# PCB.net
KiCad netlist of a schematic drawn in EasyEDA Pro
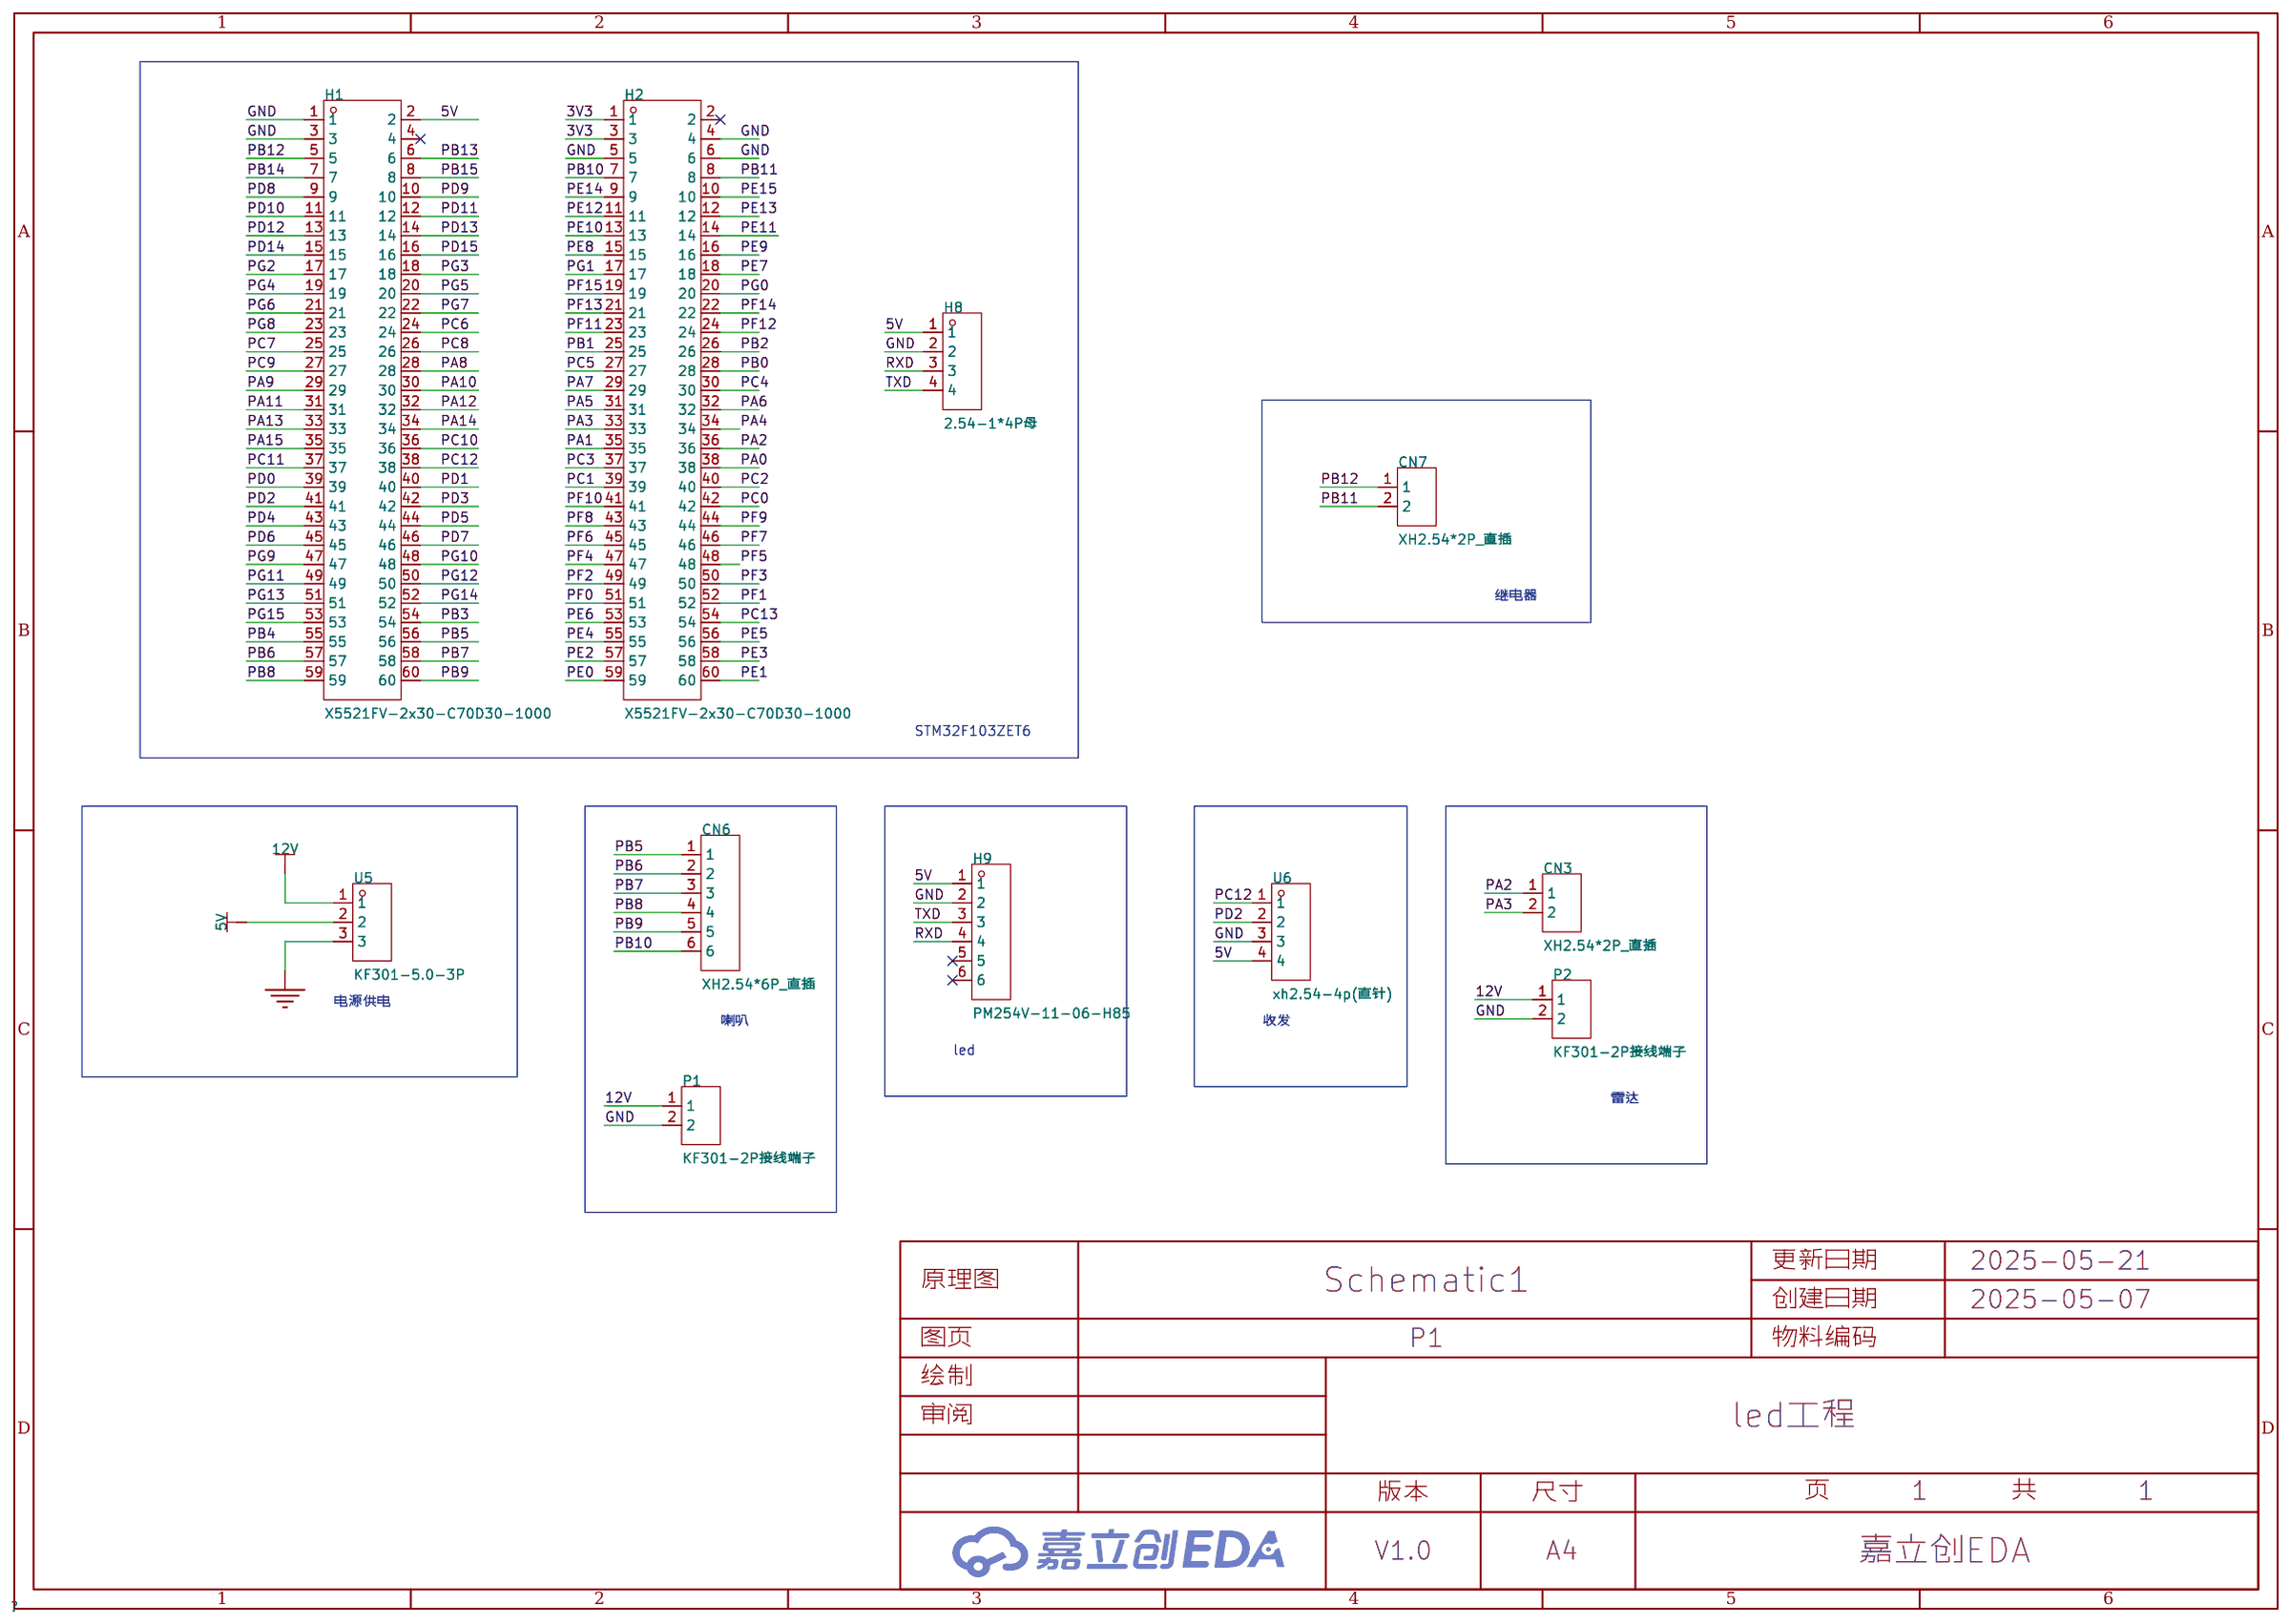
[diagram p0: schematic sheet]

(export (version "E")
  (design (tool "Eeschema 10.0.6"))
  (components
    (comp (ref "CN3")
      (value "XH2.54*2P_直插")
      (footprint "easyedapro:CONN-TH_2P-P2.50-XH2.54-2P")
      (libsource (lib "easyedapro") (part "XH2.54*2P_直插"))
    )
    (comp (ref "CN6")
      (value "XH2.54*6P_直插")
      (footprint "easyedapro:CONN-TH_XH2.54-6P")
      (libsource (lib "easyedapro") (part "XH2.54*6P_直插"))
    )
    (comp (ref "CN7")
      (value "XH2.54*2P_直插")
      (footprint "easyedapro:CONN-TH_2P-P2.50-XH2.54-2P")
      (libsource (lib "easyedapro") (part "XH2.54*2P_直插"))
    )
    (comp (ref "H1")
      (value "X5521FV-2x30-C70D30-1000")
      (footprint "easyedapro:HDR-TH_60P-P2.54-V-F-R2-C30-S2.54-3")
      (fields (field (name "Manufacturer") "XKB Connectivity(中国星坤)"))
      (libsource (lib "easyedapro") (part "X5521FV-2X30-C70D30-1000"))
    )
    (comp (ref "H2")
      (value "X5521FV-2x30-C70D30-1000")
      (footprint "easyedapro:HDR-TH_60P-P2.54-V-F-R2-C30-S2.54-3")
      (fields (field (name "Manufacturer") "XKB Connectivity(中国星坤)"))
      (libsource (lib "easyedapro") (part "X5521FV-2X30-C70D30-1000"))
    )
    (comp (ref "H8")
      (value "2.54-1*4P母")
      (footprint "easyedapro:HDR-TH_4P-P2.54-V-F")
      (fields (field (name "Manufacturer") "BOOMELE(博穆精密)"))
      (libsource (lib "easyedapro") (part "2.54-1*4P母"))
    )
    (comp (ref "H9")
      (value "PM254V-11-06-H85")
      (footprint "easyedapro:HDR-TH_6P-P2.54-V-F")
      (fields (field (name "Manufacturer") "XFCN(兴飞)"))
      (libsource (lib "easyedapro") (part "PM254V-11-06-H85"))
    )
    (comp (ref "P1")
      (value "KF301-2P接线端子")
      (footprint "easyedapro:CONN-TH_XY301V-A-5.0-2P")
      (libsource (lib "easyedapro") (part "KF301-2P接线端子"))
    )
    (comp (ref "P2")
      (value "KF301-2P接线端子")
      (footprint "easyedapro:CONN-TH_XY301V-A-5.0-2P")
      (libsource (lib "easyedapro") (part "KF301-2P接线端子"))
    )
    (comp (ref "U5")
      (value "KF301-5.0-3P")
      (footprint "easyedapro:CONN-TH_3P-P5.00_KF301-5.0-3P")
      (fields (field (name "Manufacturer") "KEFA(科发)"))
      (libsource (lib "easyedapro") (part "KF301-5.0-3P"))
    )
    (comp (ref "U6")
      (value "xh2.54-4p(直针)")
      (footprint "easyedapro:CONN-TH_4P-P2.50-XH2.54-4P")
      (libsource (lib "easyedapro") (part "XH2.54-4P(直针)"))
    )
  )
  (nets
    (net (code "1") (name "/3V3") (class "Default")
      (node (ref "H2") (pin "1") (pinfunction "1_1") (pintype "unspecified"))
      (node (ref "H2") (pin "3") (pinfunction "3_3") (pintype "unspecified"))
    )
    (net (code "2") (name "/PA0") (class "Default")
      (node (ref "H2") (pin "38") (pinfunction "38_38") (pintype "unspecified"))
    )
    (net (code "3") (name "/PA1") (class "Default")
      (node (ref "H2") (pin "35") (pinfunction "35_35") (pintype "unspecified"))
    )
    (net (code "4") (name "/PA2") (class "Default")
      (node (ref "CN3") (pin "1") (pinfunction "1_1") (pintype "unspecified"))
      (node (ref "H2") (pin "36") (pinfunction "36_36") (pintype "unspecified"))
    )
    (net (code "5") (name "/PA3") (class "Default")
      (node (ref "CN3") (pin "2") (pinfunction "2_2") (pintype "unspecified"))
      (node (ref "H2") (pin "33") (pinfunction "33_33") (pintype "unspecified"))
    )
    (net (code "6") (name "/PA4") (class "Default")
      (node (ref "H2") (pin "34") (pinfunction "34_34") (pintype "unspecified"))
    )
    (net (code "7") (name "/PA5") (class "Default")
      (node (ref "H2") (pin "31") (pinfunction "31_31") (pintype "unspecified"))
    )
    (net (code "8") (name "/PA6") (class "Default")
      (node (ref "H2") (pin "32") (pinfunction "32_32") (pintype "unspecified"))
    )
    (net (code "9") (name "/PA7") (class "Default")
      (node (ref "H2") (pin "29") (pinfunction "29_29") (pintype "unspecified"))
    )
    (net (code "10") (name "/PA8") (class "Default")
      (node (ref "H1") (pin "28") (pinfunction "28_28") (pintype "unspecified"))
    )
    (net (code "11") (name "/PA9") (class "Default")
      (node (ref "H1") (pin "29") (pinfunction "29_29") (pintype "unspecified"))
    )
    (net (code "12") (name "/PA10") (class "Default")
      (node (ref "H1") (pin "30") (pinfunction "30_30") (pintype "unspecified"))
    )
    (net (code "13") (name "/PA11") (class "Default")
      (node (ref "H1") (pin "31") (pinfunction "31_31") (pintype "unspecified"))
    )
    (net (code "14") (name "/PA12") (class "Default")
      (node (ref "H1") (pin "32") (pinfunction "32_32") (pintype "unspecified"))
    )
    (net (code "15") (name "/PA13") (class "Default")
      (node (ref "H1") (pin "33") (pinfunction "33_33") (pintype "unspecified"))
    )
    (net (code "16") (name "/PA14") (class "Default")
      (node (ref "H1") (pin "34") (pinfunction "34_34") (pintype "unspecified"))
    )
    (net (code "17") (name "/PA15") (class "Default")
      (node (ref "H1") (pin "35") (pinfunction "35_35") (pintype "unspecified"))
    )
    (net (code "18") (name "/PB0") (class "Default")
      (node (ref "H2") (pin "28") (pinfunction "28_28") (pintype "unspecified"))
    )
    (net (code "19") (name "/PB1") (class "Default")
      (node (ref "H2") (pin "25") (pinfunction "25_25") (pintype "unspecified"))
    )
    (net (code "20") (name "/PB2") (class "Default")
      (node (ref "H2") (pin "26") (pinfunction "26_26") (pintype "unspecified"))
    )
    (net (code "21") (name "/PB3") (class "Default")
      (node (ref "H1") (pin "54") (pinfunction "54_54") (pintype "unspecified"))
    )
    (net (code "22") (name "/PB4") (class "Default")
      (node (ref "H1") (pin "55") (pinfunction "55_55") (pintype "unspecified"))
    )
    (net (code "23") (name "/PB5") (class "Default")
      (node (ref "CN6") (pin "1") (pinfunction "1_1") (pintype "unspecified"))
      (node (ref "H1") (pin "56") (pinfunction "56_56") (pintype "unspecified"))
    )
    (net (code "24") (name "/PB6") (class "Default")
      (node (ref "CN6") (pin "2") (pinfunction "2_2") (pintype "unspecified"))
      (node (ref "H1") (pin "57") (pinfunction "57_57") (pintype "unspecified"))
    )
    (net (code "25") (name "/PB7") (class "Default")
      (node (ref "CN6") (pin "3") (pinfunction "3_3") (pintype "unspecified"))
      (node (ref "H1") (pin "58") (pinfunction "58_58") (pintype "unspecified"))
    )
    (net (code "26") (name "/PB8") (class "Default")
      (node (ref "CN6") (pin "4") (pinfunction "4_4") (pintype "unspecified"))
      (node (ref "H1") (pin "59") (pinfunction "59_59") (pintype "unspecified"))
    )
    (net (code "27") (name "/PB9") (class "Default")
      (node (ref "CN6") (pin "5") (pinfunction "5_5") (pintype "unspecified"))
      (node (ref "H1") (pin "60") (pinfunction "60_60") (pintype "unspecified"))
    )
    (net (code "28") (name "/PB10") (class "Default")
      (node (ref "CN6") (pin "6") (pinfunction "6_6") (pintype "unspecified"))
      (node (ref "H2") (pin "7") (pinfunction "7_7") (pintype "unspecified"))
    )
    (net (code "29") (name "/PB11") (class "Default")
      (node (ref "CN7") (pin "2") (pinfunction "2_2") (pintype "unspecified"))
      (node (ref "H2") (pin "8") (pinfunction "8_8") (pintype "unspecified"))
    )
    (net (code "30") (name "/PB12") (class "Default")
      (node (ref "CN7") (pin "1") (pinfunction "1_1") (pintype "unspecified"))
      (node (ref "H1") (pin "5") (pinfunction "5_5") (pintype "unspecified"))
    )
    (net (code "31") (name "/PB13") (class "Default")
      (node (ref "H1") (pin "6") (pinfunction "6_6") (pintype "unspecified"))
    )
    (net (code "32") (name "/PB14") (class "Default")
      (node (ref "H1") (pin "7") (pinfunction "7_7") (pintype "unspecified"))
    )
    (net (code "33") (name "/PB15") (class "Default")
      (node (ref "H1") (pin "8") (pinfunction "8_8") (pintype "unspecified"))
    )
    (net (code "34") (name "/PC0") (class "Default")
      (node (ref "H2") (pin "42") (pinfunction "42_42") (pintype "unspecified"))
    )
    (net (code "35") (name "/PC1") (class "Default")
      (node (ref "H2") (pin "39") (pinfunction "39_39") (pintype "unspecified"))
    )
    (net (code "36") (name "/PC2") (class "Default")
      (node (ref "H2") (pin "40") (pinfunction "40_40") (pintype "unspecified"))
    )
    (net (code "37") (name "/PC3") (class "Default")
      (node (ref "H2") (pin "37") (pinfunction "37_37") (pintype "unspecified"))
    )
    (net (code "38") (name "/PC4") (class "Default")
      (node (ref "H2") (pin "30") (pinfunction "30_30") (pintype "unspecified"))
    )
    (net (code "39") (name "/PC5") (class "Default")
      (node (ref "H2") (pin "27") (pinfunction "27_27") (pintype "unspecified"))
    )
    (net (code "40") (name "/PC6") (class "Default")
      (node (ref "H1") (pin "24") (pinfunction "24_24") (pintype "unspecified"))
    )
    (net (code "41") (name "/PC7") (class "Default")
      (node (ref "H1") (pin "25") (pinfunction "25_25") (pintype "unspecified"))
    )
    (net (code "42") (name "/PC8") (class "Default")
      (node (ref "H1") (pin "26") (pinfunction "26_26") (pintype "unspecified"))
    )
    (net (code "43") (name "/PC9") (class "Default")
      (node (ref "H1") (pin "27") (pinfunction "27_27") (pintype "unspecified"))
    )
    (net (code "44") (name "/PC10") (class "Default")
      (node (ref "H1") (pin "36") (pinfunction "36_36") (pintype "unspecified"))
    )
    (net (code "45") (name "/PC11") (class "Default")
      (node (ref "H1") (pin "37") (pinfunction "37_37") (pintype "unspecified"))
    )
    (net (code "46") (name "/PC12") (class "Default")
      (node (ref "H1") (pin "38") (pinfunction "38_38") (pintype "unspecified"))
      (node (ref "U6") (pin "1") (pinfunction "1_1") (pintype "unspecified"))
    )
    (net (code "47") (name "/PC13") (class "Default")
      (node (ref "H2") (pin "54") (pinfunction "54_54") (pintype "unspecified"))
    )
    (net (code "48") (name "/PD0") (class "Default")
      (node (ref "H1") (pin "39") (pinfunction "39_39") (pintype "unspecified"))
    )
    (net (code "49") (name "/PD1") (class "Default")
      (node (ref "H1") (pin "40") (pinfunction "40_40") (pintype "unspecified"))
    )
    (net (code "50") (name "/PD2") (class "Default")
      (node (ref "H1") (pin "41") (pinfunction "41_41") (pintype "unspecified"))
      (node (ref "U6") (pin "2") (pinfunction "2_2") (pintype "unspecified"))
    )
    (net (code "51") (name "/PD3") (class "Default")
      (node (ref "H1") (pin "42") (pinfunction "42_42") (pintype "unspecified"))
    )
    (net (code "52") (name "/PD4") (class "Default")
      (node (ref "H1") (pin "43") (pinfunction "43_43") (pintype "unspecified"))
    )
    (net (code "53") (name "/PD5") (class "Default")
      (node (ref "H1") (pin "44") (pinfunction "44_44") (pintype "unspecified"))
    )
    (net (code "54") (name "/PD6") (class "Default")
      (node (ref "H1") (pin "45") (pinfunction "45_45") (pintype "unspecified"))
    )
    (net (code "55") (name "/PD7") (class "Default")
      (node (ref "H1") (pin "46") (pinfunction "46_46") (pintype "unspecified"))
    )
    (net (code "56") (name "/PD8") (class "Default")
      (node (ref "H1") (pin "9") (pinfunction "9_9") (pintype "unspecified"))
    )
    (net (code "57") (name "/PD9") (class "Default")
      (node (ref "H1") (pin "10") (pinfunction "10_10") (pintype "unspecified"))
    )
    (net (code "58") (name "/PD10") (class "Default")
      (node (ref "H1") (pin "11") (pinfunction "11_11") (pintype "unspecified"))
    )
    (net (code "59") (name "/PD11") (class "Default")
      (node (ref "H1") (pin "12") (pinfunction "12_12") (pintype "unspecified"))
    )
    (net (code "60") (name "/PD12") (class "Default")
      (node (ref "H1") (pin "13") (pinfunction "13_13") (pintype "unspecified"))
    )
    (net (code "61") (name "/PD13") (class "Default")
      (node (ref "H1") (pin "14") (pinfunction "14_14") (pintype "unspecified"))
    )
    (net (code "62") (name "/PD14") (class "Default")
      (node (ref "H1") (pin "15") (pinfunction "15_15") (pintype "unspecified"))
    )
    (net (code "63") (name "/PD15") (class "Default")
      (node (ref "H1") (pin "16") (pinfunction "16_16") (pintype "unspecified"))
    )
    (net (code "64") (name "/PE0") (class "Default")
      (node (ref "H2") (pin "59") (pinfunction "59_59") (pintype "unspecified"))
    )
    (net (code "65") (name "/PE1") (class "Default")
      (node (ref "H2") (pin "60") (pinfunction "60_60") (pintype "unspecified"))
    )
    (net (code "66") (name "/PE2") (class "Default")
      (node (ref "H2") (pin "57") (pinfunction "57_57") (pintype "unspecified"))
    )
    (net (code "67") (name "/PE3") (class "Default")
      (node (ref "H2") (pin "58") (pinfunction "58_58") (pintype "unspecified"))
    )
    (net (code "68") (name "/PE4") (class "Default")
      (node (ref "H2") (pin "55") (pinfunction "55_55") (pintype "unspecified"))
    )
    (net (code "69") (name "/PE5") (class "Default")
      (node (ref "H2") (pin "56") (pinfunction "56_56") (pintype "unspecified"))
    )
    (net (code "70") (name "/PE6") (class "Default")
      (node (ref "H2") (pin "53") (pinfunction "53_53") (pintype "unspecified"))
    )
    (net (code "71") (name "/PE7") (class "Default")
      (node (ref "H2") (pin "18") (pinfunction "18_18") (pintype "unspecified"))
    )
    (net (code "72") (name "/PE8") (class "Default")
      (node (ref "H2") (pin "15") (pinfunction "15_15") (pintype "unspecified"))
    )
    (net (code "73") (name "/PE9") (class "Default")
      (node (ref "H2") (pin "16") (pinfunction "16_16") (pintype "unspecified"))
    )
    (net (code "74") (name "/PE10") (class "Default")
      (node (ref "H2") (pin "13") (pinfunction "13_13") (pintype "unspecified"))
    )
    (net (code "75") (name "/PE11") (class "Default")
      (node (ref "H2") (pin "14") (pinfunction "14_14") (pintype "unspecified"))
    )
    (net (code "76") (name "/PE12") (class "Default")
      (node (ref "H2") (pin "11") (pinfunction "11_11") (pintype "unspecified"))
    )
    (net (code "77") (name "/PE13") (class "Default")
      (node (ref "H2") (pin "12") (pinfunction "12_12") (pintype "unspecified"))
    )
    (net (code "78") (name "/PE14") (class "Default")
      (node (ref "H2") (pin "9") (pinfunction "9_9") (pintype "unspecified"))
    )
    (net (code "79") (name "/PE15") (class "Default")
      (node (ref "H2") (pin "10") (pinfunction "10_10") (pintype "unspecified"))
    )
    (net (code "80") (name "/PF0") (class "Default")
      (node (ref "H2") (pin "51") (pinfunction "51_51") (pintype "unspecified"))
    )
    (net (code "81") (name "/PF1") (class "Default")
      (node (ref "H2") (pin "52") (pinfunction "52_52") (pintype "unspecified"))
    )
    (net (code "82") (name "/PF2") (class "Default")
      (node (ref "H2") (pin "49") (pinfunction "49_49") (pintype "unspecified"))
    )
    (net (code "83") (name "/PF3") (class "Default")
      (node (ref "H2") (pin "50") (pinfunction "50_50") (pintype "unspecified"))
    )
    (net (code "84") (name "/PF4") (class "Default")
      (node (ref "H2") (pin "47") (pinfunction "47_47") (pintype "unspecified"))
    )
    (net (code "85") (name "/PF5") (class "Default")
      (node (ref "H2") (pin "48") (pinfunction "48_48") (pintype "unspecified"))
    )
    (net (code "86") (name "/PF6") (class "Default")
      (node (ref "H2") (pin "45") (pinfunction "45_45") (pintype "unspecified"))
    )
    (net (code "87") (name "/PF7") (class "Default")
      (node (ref "H2") (pin "46") (pinfunction "46_46") (pintype "unspecified"))
    )
    (net (code "88") (name "/PF8") (class "Default")
      (node (ref "H2") (pin "43") (pinfunction "43_43") (pintype "unspecified"))
    )
    (net (code "89") (name "/PF9") (class "Default")
      (node (ref "H2") (pin "44") (pinfunction "44_44") (pintype "unspecified"))
    )
    (net (code "90") (name "/PF10") (class "Default")
      (node (ref "H2") (pin "41") (pinfunction "41_41") (pintype "unspecified"))
    )
    (net (code "91") (name "/PF11") (class "Default")
      (node (ref "H2") (pin "23") (pinfunction "23_23") (pintype "unspecified"))
    )
    (net (code "92") (name "/PF12") (class "Default")
      (node (ref "H2") (pin "24") (pinfunction "24_24") (pintype "unspecified"))
    )
    (net (code "93") (name "/PF13") (class "Default")
      (node (ref "H2") (pin "21") (pinfunction "21_21") (pintype "unspecified"))
    )
    (net (code "94") (name "/PF14") (class "Default")
      (node (ref "H2") (pin "22") (pinfunction "22_22") (pintype "unspecified"))
    )
    (net (code "95") (name "/PF15") (class "Default")
      (node (ref "H2") (pin "19") (pinfunction "19_19") (pintype "unspecified"))
    )
    (net (code "96") (name "/PG0") (class "Default")
      (node (ref "H2") (pin "20") (pinfunction "20_20") (pintype "unspecified"))
    )
    (net (code "97") (name "/PG1") (class "Default")
      (node (ref "H2") (pin "17") (pinfunction "17_17") (pintype "unspecified"))
    )
    (net (code "98") (name "/PG2") (class "Default")
      (node (ref "H1") (pin "17") (pinfunction "17_17") (pintype "unspecified"))
    )
    (net (code "99") (name "/PG3") (class "Default")
      (node (ref "H1") (pin "18") (pinfunction "18_18") (pintype "unspecified"))
    )
    (net (code "100") (name "/PG4") (class "Default")
      (node (ref "H1") (pin "19") (pinfunction "19_19") (pintype "unspecified"))
    )
    (net (code "101") (name "/PG5") (class "Default")
      (node (ref "H1") (pin "20") (pinfunction "20_20") (pintype "unspecified"))
    )
    (net (code "102") (name "/PG6") (class "Default")
      (node (ref "H1") (pin "21") (pinfunction "21_21") (pintype "unspecified"))
    )
    (net (code "103") (name "/PG7") (class "Default")
      (node (ref "H1") (pin "22") (pinfunction "22_22") (pintype "unspecified"))
    )
    (net (code "104") (name "/PG8") (class "Default")
      (node (ref "H1") (pin "23") (pinfunction "23_23") (pintype "unspecified"))
    )
    (net (code "105") (name "/PG9") (class "Default")
      (node (ref "H1") (pin "47") (pinfunction "47_47") (pintype "unspecified"))
    )
    (net (code "106") (name "/PG10") (class "Default")
      (node (ref "H1") (pin "48") (pinfunction "48_48") (pintype "unspecified"))
    )
    (net (code "107") (name "/PG11") (class "Default")
      (node (ref "H1") (pin "49") (pinfunction "49_49") (pintype "unspecified"))
    )
    (net (code "108") (name "/PG12") (class "Default")
      (node (ref "H1") (pin "50") (pinfunction "50_50") (pintype "unspecified"))
    )
    (net (code "109") (name "/PG13") (class "Default")
      (node (ref "H1") (pin "51") (pinfunction "51_51") (pintype "unspecified"))
    )
    (net (code "110") (name "/PG14") (class "Default")
      (node (ref "H1") (pin "52") (pinfunction "52_52") (pintype "unspecified"))
    )
    (net (code "111") (name "/PG15") (class "Default")
      (node (ref "H1") (pin "53") (pinfunction "53_53") (pintype "unspecified"))
    )
    (net (code "112") (name "/RXD") (class "Default")
      (node (ref "H8") (pin "3") (pinfunction "3_3") (pintype "unspecified"))
      (node (ref "H9") (pin "4") (pinfunction "4_4") (pintype "unspecified"))
    )
    (net (code "113") (name "/TXD") (class "Default")
      (node (ref "H8") (pin "4") (pinfunction "4_4") (pintype "unspecified"))
      (node (ref "H9") (pin "3") (pinfunction "3_3") (pintype "unspecified"))
    )
    (net (code "114") (name "5V") (class "Default")
      (node (ref "H1") (pin "2") (pinfunction "2_2") (pintype "unspecified"))
      (node (ref "H8") (pin "1") (pinfunction "1_1") (pintype "unspecified"))
      (node (ref "H9") (pin "1") (pinfunction "1_1") (pintype "unspecified"))
      (node (ref "U5") (pin "2") (pinfunction "2_2") (pintype "unspecified"))
      (node (ref "U6") (pin "4") (pinfunction "4_4") (pintype "unspecified"))
    )
    (net (code "115") (name "12V") (class "Default")
      (node (ref "P1") (pin "1") (pinfunction "1_1") (pintype "unspecified"))
      (node (ref "P2") (pin "1") (pinfunction "1_1") (pintype "unspecified"))
      (node (ref "U5") (pin "1") (pinfunction "1_1") (pintype "unspecified"))
    )
    (net (code "116") (name "GND") (class "Default")
      (node (ref "H1") (pin "1") (pinfunction "1_1") (pintype "unspecified"))
      (node (ref "H1") (pin "3") (pinfunction "3_3") (pintype "unspecified"))
      (node (ref "H2") (pin "4") (pinfunction "4_4") (pintype "unspecified"))
      (node (ref "H2") (pin "5") (pinfunction "5_5") (pintype "unspecified"))
      (node (ref "H2") (pin "6") (pinfunction "6_6") (pintype "unspecified"))
      (node (ref "H8") (pin "2") (pinfunction "2_2") (pintype "unspecified"))
      (node (ref "H9") (pin "2") (pinfunction "2_2") (pintype "unspecified"))
      (node (ref "P1") (pin "2") (pinfunction "2_2") (pintype "unspecified"))
      (node (ref "P2") (pin "2") (pinfunction "2_2") (pintype "unspecified"))
      (node (ref "U5") (pin "3") (pinfunction "3_3") (pintype "unspecified"))
      (node (ref "U6") (pin "3") (pinfunction "3_3") (pintype "unspecified"))
    )
    (net (code "117") (name "unconnected-(H1-Pad4)") (class "Default")
      (node (ref "H1") (pin "4") (pinfunction "4_4") (pintype "unspecified+no_connect"))
    )
    (net (code "118") (name "unconnected-(H2-Pad2)") (class "Default")
      (node (ref "H2") (pin "2") (pinfunction "2_2") (pintype "unspecified+no_connect"))
    )
    (net (code "119") (name "unconnected-(H9-Pad5)") (class "Default")
      (node (ref "H9") (pin "5") (pinfunction "5_5") (pintype "unspecified+no_connect"))
    )
    (net (code "120") (name "unconnected-(H9-Pad6)") (class "Default")
      (node (ref "H9") (pin "6") (pinfunction "6_6") (pintype "unspecified+no_connect"))
    )
  )
)
